# stim_rev_I_RECT.net
KiCad netlist of a schematic drawn in EAGLE
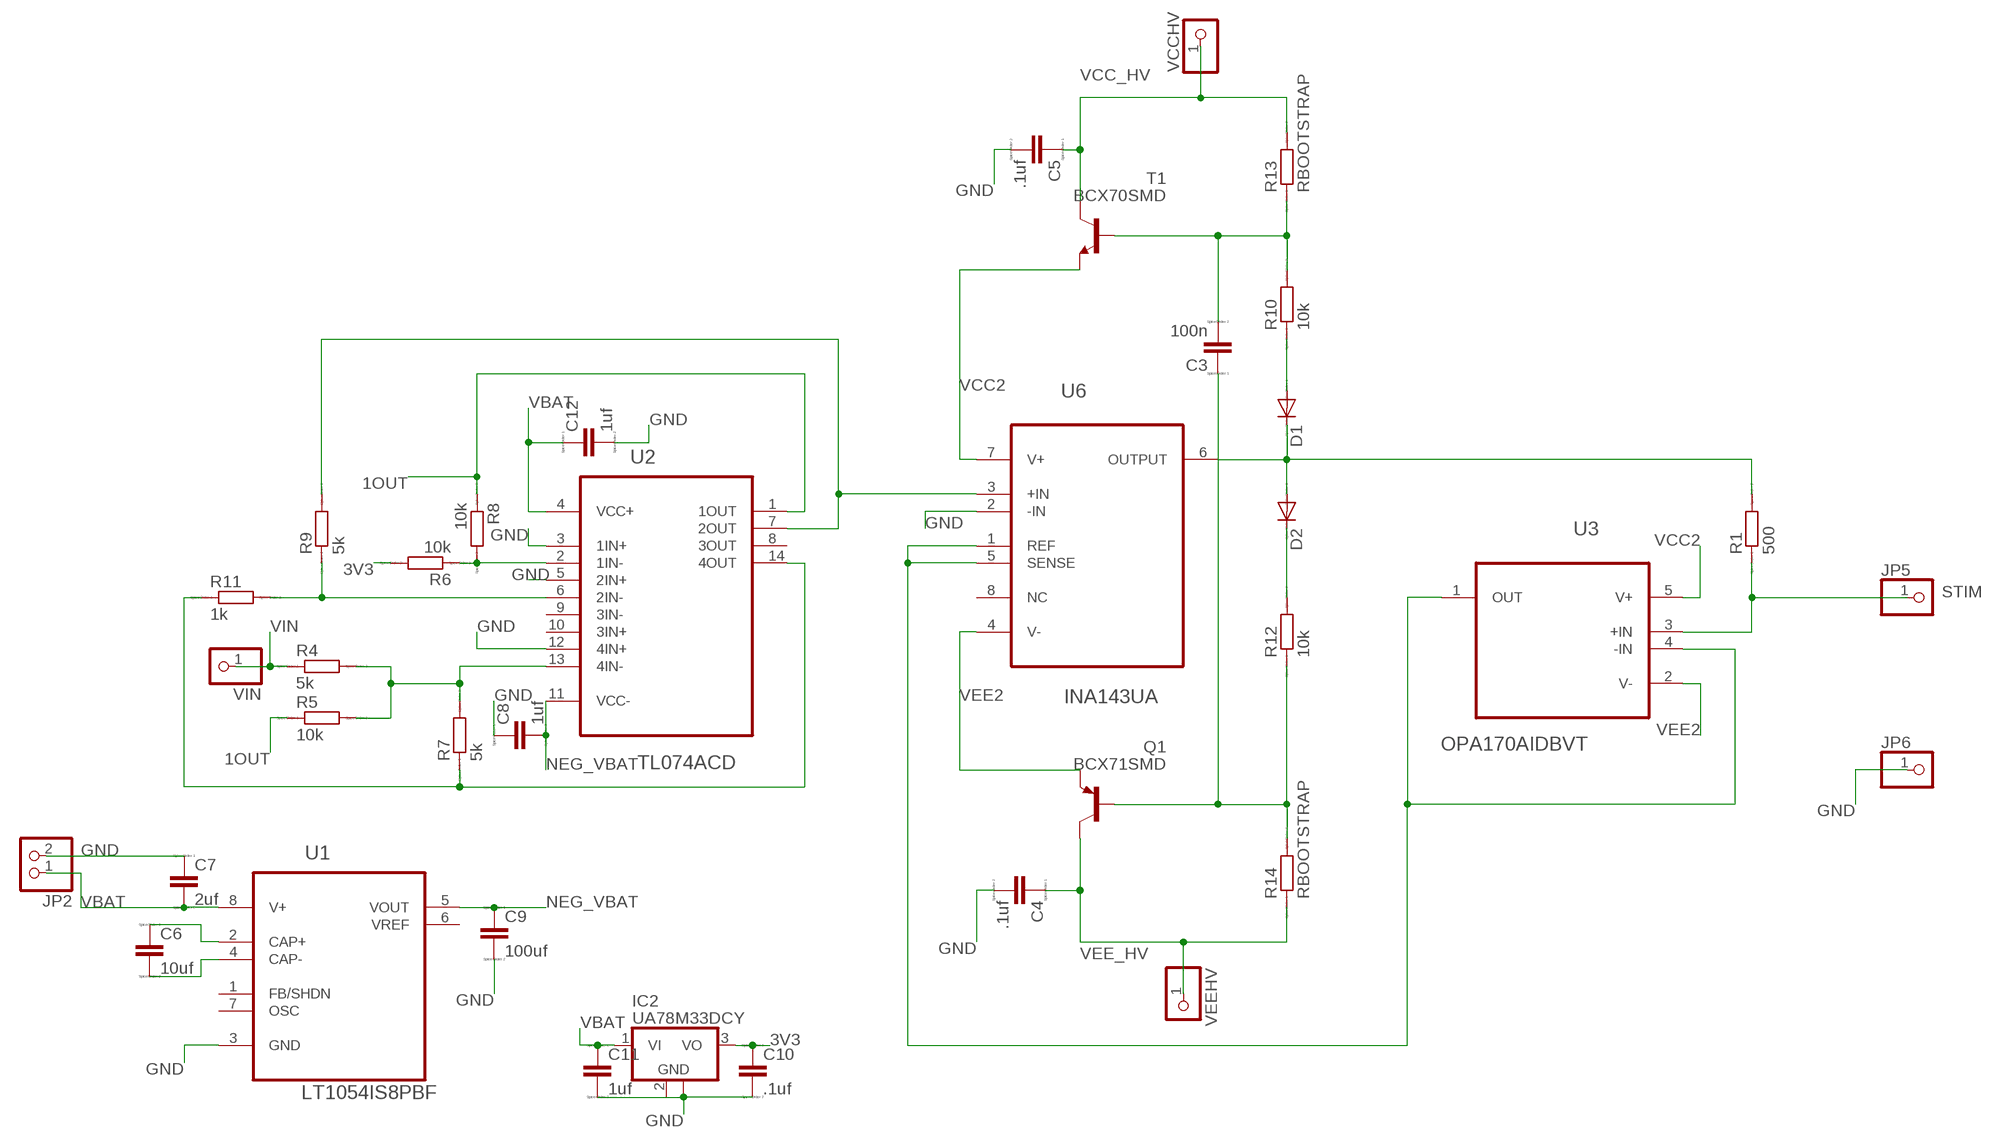
[diagram p0: schematic, sheet 1]

(export (version "E")
  (design (tool "Eeschema 10.0.6"))
  (components
    (comp (ref "C3")
      (value "100n")
      (footprint "eagle-import:C0603")
      (libsource (lib "eagle-import") (part "CC0603"))
    )
    (comp (ref "C4")
      (value ".1uf")
      (footprint "eagle-import:C0603")
      (libsource (lib "eagle-import") (part "CC0603"))
    )
    (comp (ref "C5")
      (value ".1uf")
      (footprint "eagle-import:C0603")
      (libsource (lib "eagle-import") (part "CC0603"))
    )
    (comp (ref "C6")
      (value "10uf")
      (footprint "eagle-import:C0603")
      (libsource (lib "eagle-import") (part "CC0603"))
    )
    (comp (ref "C7")
      (value "2uf")
      (footprint "eagle-import:C0603")
      (libsource (lib "eagle-import") (part "CC0603"))
    )
    (comp (ref "C8")
      (value "1uf")
      (footprint "eagle-import:C0603")
      (libsource (lib "eagle-import") (part "CC0603"))
    )
    (comp (ref "C9")
      (value "100uf")
      (footprint "eagle-import:C1210")
      (libsource (lib "eagle-import") (part "CC1210"))
    )
    (comp (ref "C10")
      (value ".1uf")
      (footprint "eagle-import:C0402")
      (libsource (lib "eagle-import") (part "CC0402"))
    )
    (comp (ref "C11")
      (value "1uf")
      (footprint "eagle-import:C0603")
      (libsource (lib "eagle-import") (part "CC0603"))
    )
    (comp (ref "C12")
      (value "1uf")
      (footprint "eagle-import:C0603")
      (libsource (lib "eagle-import") (part "CC0603"))
    )
    (comp (ref "D1")
      (value "DIODE-DO214AA")
      (footprint "eagle-import:DO214AA")
      (libsource (lib "eagle-import") (part "DIODE-DO214AA"))
    )
    (comp (ref "D2")
      (value "DIODE-DO214AA")
      (footprint "eagle-import:DO214AA")
      (libsource (lib "eagle-import") (part "DIODE-DO214AA"))
    )
    (comp (ref "IC2")
      (value "UA78M33DCY")
      (footprint "eagle-import:SOT223")
      (libsource (lib "eagle-import") (part "UA78MDCY33"))
    )
    (comp (ref "JP2")
      (value "PINHD-1X2")
      (footprint "eagle-import:1X02")
      (libsource (lib "eagle-import") (part "PINHD-1X2"))
    )
    (comp (ref "JP5")
      (value "PINHD-1X1")
      (footprint "eagle-import:1X01")
      (libsource (lib "eagle-import") (part "PINHD-1X1"))
    )
    (comp (ref "JP6")
      (value "PINHD-1X1")
      (footprint "eagle-import:1X01")
      (libsource (lib "eagle-import") (part "PINHD-1X1"))
    )
    (comp (ref "Q1")
      (value "BCX71SMD")
      (footprint "eagle-import:SOT23")
      (libsource (lib "eagle-import") (part "BCX71SMD"))
    )
    (comp (ref "R1")
      (value "500")
      (footprint "eagle-import:R0603")
      (libsource (lib "eagle-import") (part "RR0603"))
    )
    (comp (ref "R4")
      (value "5k")
      (footprint "eagle-import:R0402")
      (libsource (lib "eagle-import") (part "RR0402"))
    )
    (comp (ref "R5")
      (value "10k")
      (footprint "eagle-import:R0402")
      (libsource (lib "eagle-import") (part "RR0402"))
    )
    (comp (ref "R6")
      (value "10k")
      (footprint "eagle-import:R0402")
      (libsource (lib "eagle-import") (part "RR0402"))
    )
    (comp (ref "R7")
      (value "5k")
      (footprint "eagle-import:R0402")
      (libsource (lib "eagle-import") (part "RR0402"))
    )
    (comp (ref "R8")
      (value "10k")
      (footprint "eagle-import:R0402")
      (libsource (lib "eagle-import") (part "RR0402"))
    )
    (comp (ref "R9")
      (value "5k")
      (footprint "eagle-import:R0402")
      (libsource (lib "eagle-import") (part "RR0402"))
    )
    (comp (ref "R10")
      (value "10k")
      (footprint "eagle-import:R0603")
      (libsource (lib "eagle-import") (part "RR0603"))
    )
    (comp (ref "R11")
      (value "1k")
      (footprint "eagle-import:R0402")
      (libsource (lib "eagle-import") (part "RR0402"))
    )
    (comp (ref "R12")
      (value "10k")
      (footprint "eagle-import:R0603")
      (libsource (lib "eagle-import") (part "RR0603"))
    )
    (comp (ref "R13")
      (value "RBOOTSTRAP")
      (footprint "eagle-import:R0603")
      (libsource (lib "eagle-import") (part "RR0603"))
    )
    (comp (ref "R14")
      (value "RBOOTSTRAP")
      (footprint "eagle-import:R0603")
      (libsource (lib "eagle-import") (part "RR0603"))
    )
    (comp (ref "T1")
      (value "BCX70SMD")
      (footprint "eagle-import:SOT23")
      (libsource (lib "eagle-import") (part "BCX70SMD"))
    )
    (comp (ref "U1")
      (value "LT1054IS8PBF")
      (footprint "eagle-import:SOIC127P600X175-8N")
      (fields (field (name "MPN") "LT1054IS8#PBF"))
      (libsource (lib "eagle-import") (part "LT1054IS8PBF"))
    )
    (comp (ref "U2")
      (value "TL074ACD")
      (footprint "eagle-import:SOIC127P600X175-14N")
      (libsource (lib "eagle-import") (part "TL074ACD"))
    )
    (comp (ref "U3")
      (value "OPA170AIDBVT")
      (footprint "eagle-import:SOT95P280X145-5N")
      (libsource (lib "eagle-import") (part "OPA170AIDBVT"))
    )
    (comp (ref "U6")
      (value "INA143UA")
      (footprint "eagle-import:SOIC127P600X175-8N")
      (libsource (lib "eagle-import") (part "INA143UA"))
    )
    (comp (ref "VCCHV")
      (value "PINHD-1X1")
      (footprint "eagle-import:1X01")
      (libsource (lib "eagle-import") (part "PINHD-1X1"))
    )
    (comp (ref "VEEHV")
      (value "PINHD-1X1")
      (footprint "eagle-import:1X01")
      (libsource (lib "eagle-import") (part "PINHD-1X1"))
    )
    (comp (ref "VIN")
      (value "PINHD-1X1")
      (footprint "eagle-import:1X01")
      (libsource (lib "eagle-import") (part "PINHD-1X1"))
    )
  )
  (nets
    (net (code "1") (name "/1OUT") (class "Default")
      (node (ref "R5") (pin "1") (pinfunction "1_1") (pintype "passive"))
      (node (ref "R8") (pin "1") (pinfunction "1_1") (pintype "passive"))
      (node (ref "U2") (pin "1") (pinfunction "1OUT_1") (pintype "output"))
    )
    (net (code "2") (name "/3V3") (class "Default")
      (node (ref "C10") (pin "1") (pinfunction "1_1") (pintype "passive"))
      (node (ref "IC2") (pin "3") (pinfunction "VO_3") (pintype "passive"))
      (node (ref "R6") (pin "2") (pinfunction "2_2") (pintype "passive"))
    )
    (net (code "3") (name "/GND") (class "Default")
      (node (ref "C10") (pin "2") (pinfunction "2_2") (pintype "passive"))
      (node (ref "C11") (pin "2") (pinfunction "2_2") (pintype "passive"))
      (node (ref "C12") (pin "2") (pinfunction "2_2") (pintype "passive"))
      (node (ref "C4") (pin "2") (pinfunction "2_2") (pintype "passive"))
      (node (ref "C5") (pin "2") (pinfunction "2_2") (pintype "passive"))
      (node (ref "C7") (pin "1") (pinfunction "1_1") (pintype "passive"))
      (node (ref "C8") (pin "1") (pinfunction "1_1") (pintype "passive"))
      (node (ref "C9") (pin "2") (pinfunction "2_2") (pintype "passive"))
      (node (ref "IC2") (pin "2") (pinfunction "GND_2") (pintype "passive"))
      (node (ref "IC2") (pin "4") (pinfunction "GND_4") (pintype "passive"))
      (node (ref "JP2") (pin "2") (pinfunction "2_2") (pintype "passive"))
      (node (ref "JP6") (pin "1") (pinfunction "1_1") (pintype "passive"))
      (node (ref "U1") (pin "3") (pinfunction "GND_3") (pintype "passive"))
      (node (ref "U2") (pin "12") (pinfunction "4IN+_12") (pintype "input"))
      (node (ref "U2") (pin "3") (pinfunction "1IN+_3") (pintype "input"))
      (node (ref "U2") (pin "5") (pinfunction "2IN+_5") (pintype "input"))
      (node (ref "U6") (pin "2") (pinfunction "-IN_2") (pintype "input"))
    )
    (net (code "4") (name "/NEG_VBAT") (class "Default")
      (node (ref "C8") (pin "2") (pinfunction "2_2") (pintype "passive"))
      (node (ref "C9") (pin "1") (pinfunction "1_1") (pintype "passive"))
      (node (ref "U1") (pin "5") (pinfunction "VOUT_5") (pintype "output"))
      (node (ref "U2") (pin "11") (pinfunction "VCC-_11") (pintype "power_in"))
    )
    (net (code "5") (name "/STIM") (class "Default")
      (node (ref "JP5") (pin "1") (pinfunction "1_1") (pintype "passive"))
      (node (ref "R1") (pin "1") (pinfunction "1_1") (pintype "passive"))
      (node (ref "U3") (pin "3") (pinfunction "+IN_3") (pintype "input"))
    )
    (net (code "6") (name "/VBAT") (class "Default")
      (node (ref "C11") (pin "1") (pinfunction "1_1") (pintype "passive"))
      (node (ref "C12") (pin "1") (pinfunction "1_1") (pintype "passive"))
      (node (ref "C7") (pin "2") (pinfunction "2_2") (pintype "passive"))
      (node (ref "IC2") (pin "1") (pinfunction "VI_1") (pintype "input"))
      (node (ref "JP2") (pin "1") (pinfunction "1_1") (pintype "passive"))
      (node (ref "U1") (pin "8") (pinfunction "V+_8") (pintype "power_in"))
      (node (ref "U2") (pin "4") (pinfunction "VCC+_4") (pintype "power_in"))
    )
    (net (code "7") (name "/VCC2") (class "Default")
      (node (ref "T1") (pin "2") (pinfunction "E_2") (pintype "passive"))
      (node (ref "U3") (pin "5") (pinfunction "V+_5") (pintype "power_in"))
      (node (ref "U6") (pin "7") (pinfunction "V+_7") (pintype "power_in"))
    )
    (net (code "8") (name "/VCC_HV") (class "Default")
      (node (ref "C5") (pin "1") (pinfunction "1_1") (pintype "passive"))
      (node (ref "R13") (pin "2") (pinfunction "2_2") (pintype "passive"))
      (node (ref "T1") (pin "3") (pinfunction "C_3") (pintype "passive"))
      (node (ref "VCCHV") (pin "1") (pinfunction "1_1") (pintype "passive"))
    )
    (net (code "9") (name "/VEE2") (class "Default")
      (node (ref "Q1") (pin "2") (pinfunction "E_2") (pintype "passive"))
      (node (ref "U3") (pin "2") (pinfunction "V-_2") (pintype "passive"))
      (node (ref "U6") (pin "4") (pinfunction "V-_4") (pintype "power_in"))
    )
    (net (code "10") (name "/VEE_HV") (class "Default")
      (node (ref "C4") (pin "1") (pinfunction "1_1") (pintype "passive"))
      (node (ref "Q1") (pin "3") (pinfunction "C_3") (pintype "passive"))
      (node (ref "R14") (pin "1") (pinfunction "1_1") (pintype "passive"))
      (node (ref "VEEHV") (pin "1") (pinfunction "1_1") (pintype "passive"))
    )
    (net (code "11") (name "/VIN") (class "Default")
      (node (ref "R4") (pin "1") (pinfunction "1_1") (pintype "passive"))
      (node (ref "VIN") (pin "1") (pinfunction "1_1") (pintype "passive"))
    )
    (net (code "12") (name "Net-(D1-PadA)") (class "Default")
      (node (ref "D1") (pin "A") (pinfunction "A_A") (pintype "passive"))
      (node (ref "R10") (pin "1") (pinfunction "1_1") (pintype "passive"))
    )
    (net (code "13") (name "Net-(D2-PadC)") (class "Default")
      (node (ref "D2") (pin "C") (pinfunction "C_C") (pintype "passive"))
      (node (ref "R12") (pin "2") (pinfunction "2_2") (pintype "passive"))
    )
    (net (code "14") (name "Net-(Q1-B)") (class "Default")
      (node (ref "C3") (pin "1") (pinfunction "1_1") (pintype "passive"))
      (node (ref "Q1") (pin "1") (pinfunction "B_1") (pintype "passive"))
      (node (ref "R12") (pin "1") (pinfunction "1_1") (pintype "passive"))
      (node (ref "R14") (pin "2") (pinfunction "2_2") (pintype "passive"))
    )
    (net (code "15") (name "Net-(T1-B)") (class "Default")
      (node (ref "C3") (pin "2") (pinfunction "2_2") (pintype "passive"))
      (node (ref "R10") (pin "2") (pinfunction "2_2") (pintype "passive"))
      (node (ref "R13") (pin "1") (pinfunction "1_1") (pintype "passive"))
      (node (ref "T1") (pin "1") (pinfunction "B_1") (pintype "passive"))
    )
    (net (code "16") (name "Net-(U1-CAP+)") (class "Default")
      (node (ref "C6") (pin "1") (pinfunction "1_1") (pintype "passive"))
      (node (ref "U1") (pin "2") (pinfunction "CAP+_2") (pintype "passive"))
    )
    (net (code "17") (name "Net-(U1-CAP-)") (class "Default")
      (node (ref "C6") (pin "2") (pinfunction "2_2") (pintype "passive"))
      (node (ref "U1") (pin "4") (pinfunction "CAP-_4") (pintype "passive"))
    )
    (net (code "18") (name "Net-(U2-1IN-)") (class "Default")
      (node (ref "R6") (pin "1") (pinfunction "1_1") (pintype "passive"))
      (node (ref "R8") (pin "2") (pinfunction "2_2") (pintype "passive"))
      (node (ref "U2") (pin "2") (pinfunction "1IN-_2") (pintype "input"))
    )
    (net (code "19") (name "Net-(U2-2IN-)") (class "Default")
      (node (ref "R11") (pin "2") (pinfunction "2_2") (pintype "passive"))
      (node (ref "R9") (pin "1") (pinfunction "1_1") (pintype "passive"))
      (node (ref "U2") (pin "6") (pinfunction "2IN-_6") (pintype "input"))
    )
    (net (code "20") (name "Net-(U2-2OUT)") (class "Default")
      (node (ref "R9") (pin "2") (pinfunction "2_2") (pintype "passive"))
      (node (ref "U2") (pin "7") (pinfunction "2OUT_7") (pintype "output"))
      (node (ref "U6") (pin "3") (pinfunction "+IN_3") (pintype "input"))
    )
    (net (code "21") (name "Net-(U2-4IN-)") (class "Default")
      (node (ref "R4") (pin "2") (pinfunction "2_2") (pintype "passive"))
      (node (ref "R5") (pin "2") (pinfunction "2_2") (pintype "passive"))
      (node (ref "R7") (pin "2") (pinfunction "2_2") (pintype "passive"))
      (node (ref "U2") (pin "13") (pinfunction "4IN-_13") (pintype "input"))
    )
    (net (code "22") (name "Net-(U2-4OUT)") (class "Default")
      (node (ref "R11") (pin "1") (pinfunction "1_1") (pintype "passive"))
      (node (ref "R7") (pin "1") (pinfunction "1_1") (pintype "passive"))
      (node (ref "U2") (pin "14") (pinfunction "4OUT_14") (pintype "output"))
    )
    (net (code "23") (name "Net-(U3--IN)") (class "Default")
      (node (ref "U3") (pin "1") (pinfunction "OUT_1") (pintype "output"))
      (node (ref "U3") (pin "4") (pinfunction "-IN_4") (pintype "input"))
      (node (ref "U6") (pin "1") (pinfunction "REF_1") (pintype "passive"))
      (node (ref "U6") (pin "5") (pinfunction "SENSE_5") (pintype "passive"))
    )
    (net (code "24") (name "Net-(U6-OUTPUT)") (class "Default")
      (node (ref "D1") (pin "C") (pinfunction "C_C") (pintype "passive"))
      (node (ref "D2") (pin "A") (pinfunction "A_A") (pintype "passive"))
      (node (ref "R1") (pin "2") (pinfunction "2_2") (pintype "passive"))
      (node (ref "U6") (pin "6") (pinfunction "OUTPUT_6") (pintype "output"))
    )
    (net (code "25") (name "unconnected-(U1-FB{slash}SHDN-Pad1)") (class "Default")
      (node (ref "U1") (pin "1") (pinfunction "FB/SHDN_1") (pintype "input"))
    )
    (net (code "26") (name "unconnected-(U1-OSC-Pad7)") (class "Default")
      (node (ref "U1") (pin "7") (pinfunction "OSC_7") (pintype "input"))
    )
    (net (code "27") (name "unconnected-(U1-VREF-Pad6)") (class "Default")
      (node (ref "U1") (pin "6") (pinfunction "VREF_6") (pintype "output"))
    )
    (net (code "28") (name "unconnected-(U2-3IN+-Pad10)") (class "Default")
      (node (ref "U2") (pin "10") (pinfunction "3IN+_10") (pintype "input"))
    )
    (net (code "29") (name "unconnected-(U2-3IN--Pad9)") (class "Default")
      (node (ref "U2") (pin "9") (pinfunction "3IN-_9") (pintype "input"))
    )
    (net (code "30") (name "unconnected-(U2-3OUT-Pad8)") (class "Default")
      (node (ref "U2") (pin "8") (pinfunction "3OUT_8") (pintype "output"))
    )
    (net (code "31") (name "unconnected-(U6-NC-Pad8)") (class "Default")
      (node (ref "U6") (pin "8") (pinfunction "NC_8") (pintype "no_connect"))
    )
  )
)
